# CHIP_tzatziffy_v6.net
KiCad netlist of a schematic drawn in EAGLE
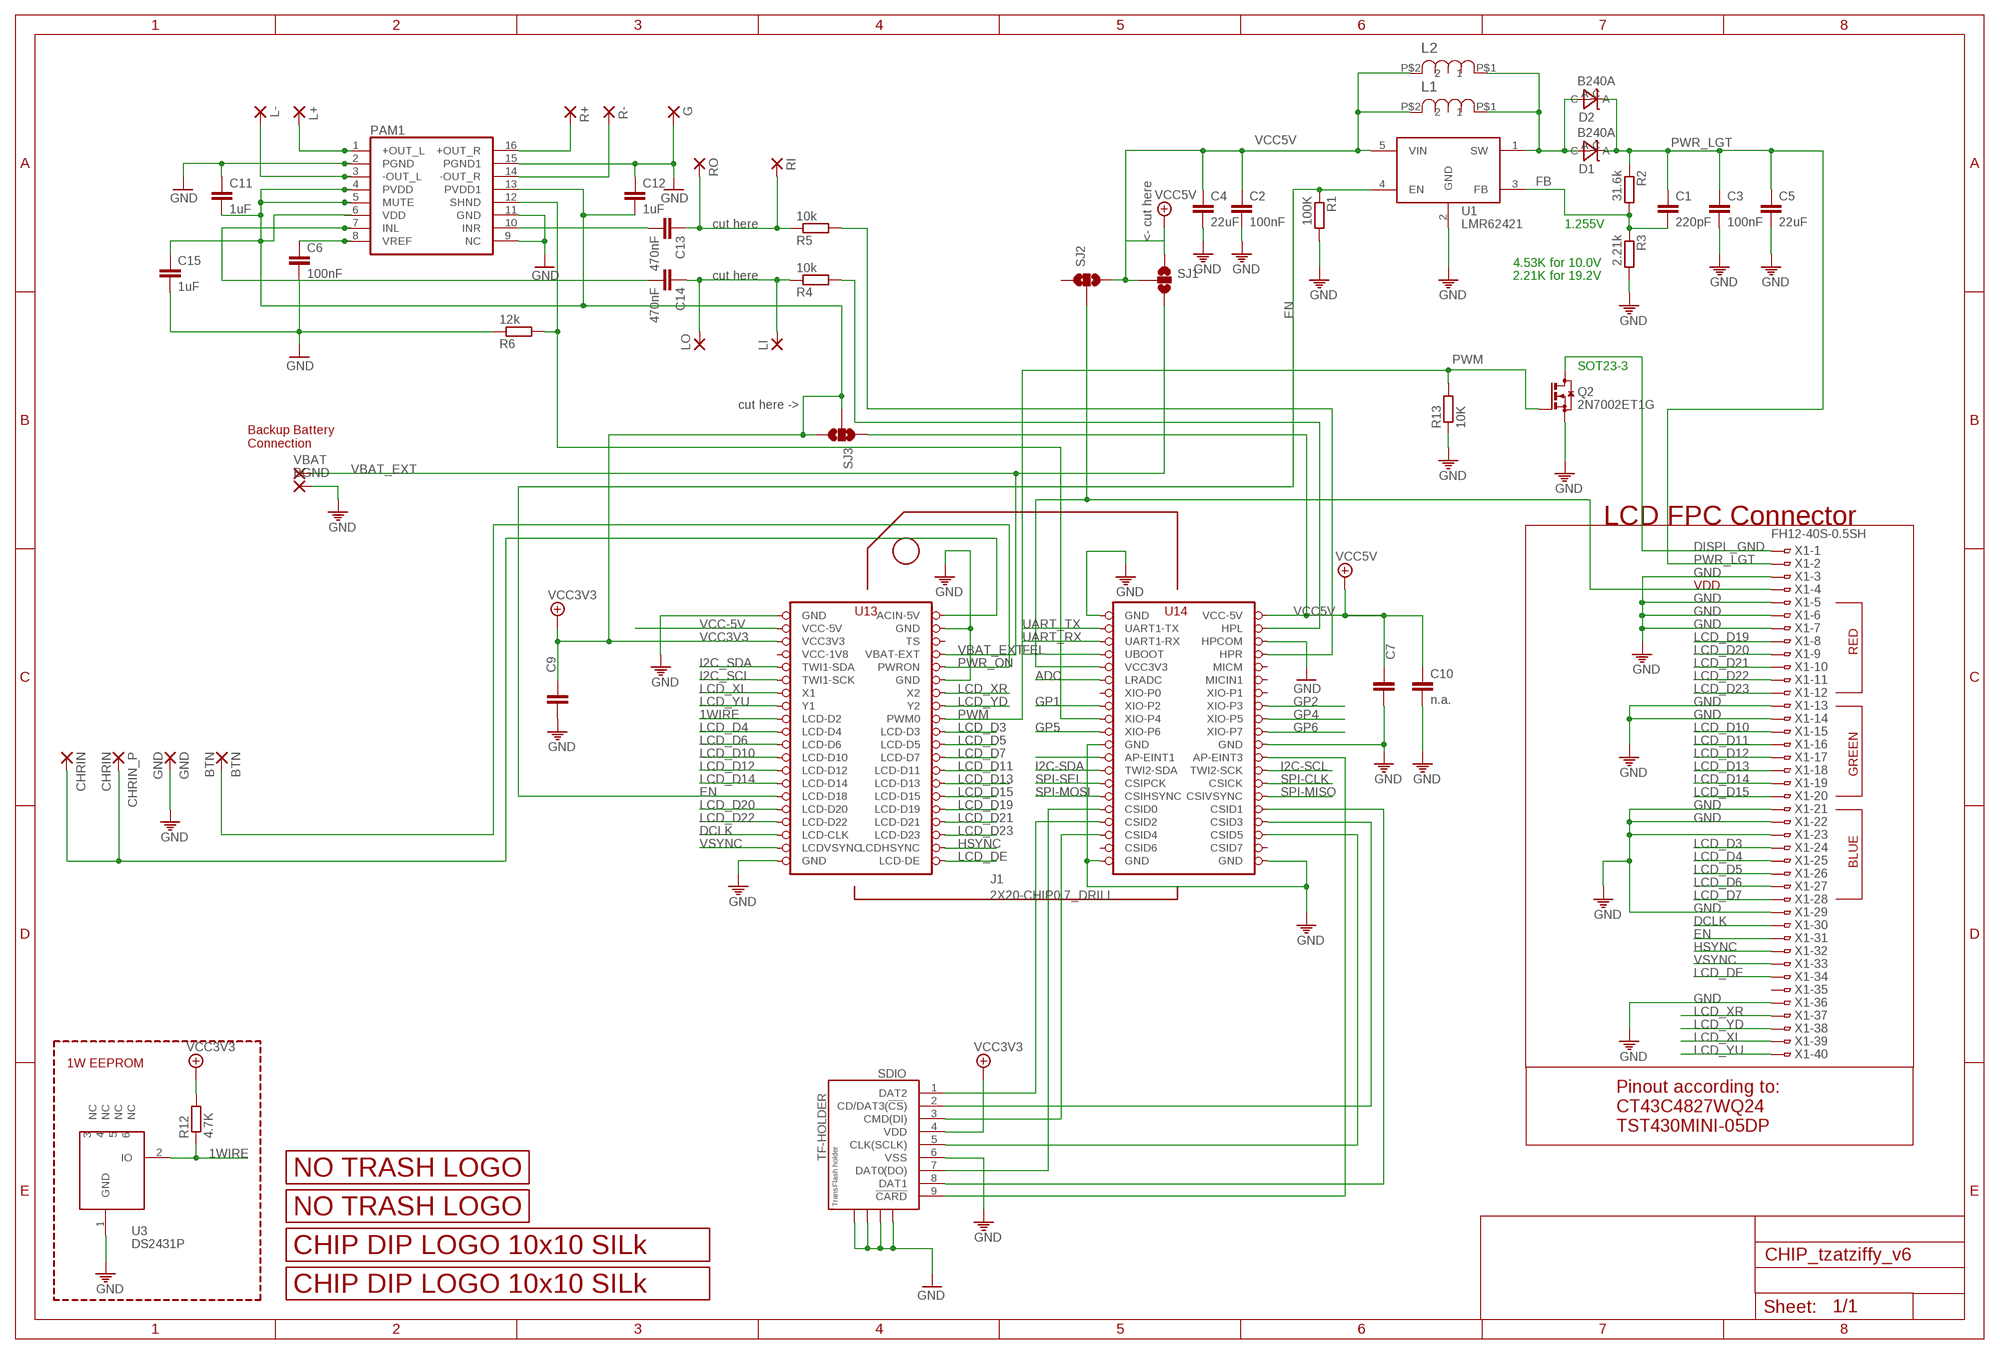
[diagram p0: schematic, sheet 1]

(export (version "E")
  (design (tool "Eeschema 10.0.6"))
  (components
    (comp (ref "BGND")
      (value "1,6/0,8")
      (footprint "eagle-import:1,6_0,8")
      (libsource (lib "eagle-import") (part "1,6/0,8"))
    )
    (comp (ref "BTN")
      (value "BTN")
      (footprint "eagle-import:SMD2,54-5,08")
      (libsource (lib "eagle-import") (part "SMD5"))
    )
    (comp (ref "C1")
      (value "220pF")
      (footprint "eagle-import:C0805")
      (libsource (lib "eagle-import") (part "C-EUC0805"))
    )
    (comp (ref "C2")
      (value "100nF")
      (footprint "eagle-import:C0805")
      (libsource (lib "eagle-import") (part "C-EUC0805"))
    )
    (comp (ref "C3")
      (value "100nF")
      (footprint "eagle-import:C0805")
      (libsource (lib "eagle-import") (part "C-EUC0805"))
    )
    (comp (ref "C4")
      (value "22uF")
      (footprint "eagle-import:C1206")
      (libsource (lib "eagle-import") (part "C-EUC1206"))
    )
    (comp (ref "C5")
      (value "22uF")
      (footprint "eagle-import:C1206")
      (libsource (lib "eagle-import") (part "C-EUC1206"))
    )
    (comp (ref "C6")
      (value "100nF")
      (footprint "eagle-import:C0805")
      (libsource (lib "eagle-import") (part "C-EUC0805"))
    )
    (comp (ref "C7")
      (value "n.a.")
      (footprint "eagle-import:C0805")
      (libsource (lib "eagle-import") (part "C-EUC0805"))
    )
    (comp (ref "C9")
      (value "n.a.")
      (footprint "eagle-import:C0805")
      (libsource (lib "eagle-import") (part "C-EUC0805"))
    )
    (comp (ref "C10")
      (value "n.a.")
      (footprint "eagle-import:C0805")
      (libsource (lib "eagle-import") (part "C-EUC0805"))
    )
    (comp (ref "C11")
      (value "1uF")
      (footprint "eagle-import:C0805")
      (libsource (lib "eagle-import") (part "C-EUC0805"))
    )
    (comp (ref "C12")
      (value "1uF")
      (footprint "eagle-import:C0805")
      (libsource (lib "eagle-import") (part "C-EUC0805"))
    )
    (comp (ref "C13")
      (value "470nF")
      (footprint "eagle-import:C0805")
      (libsource (lib "eagle-import") (part "C-EUC0805"))
    )
    (comp (ref "C14")
      (value "470nF")
      (footprint "eagle-import:C0805")
      (libsource (lib "eagle-import") (part "C-EUC0805"))
    )
    (comp (ref "C15")
      (value "1uF")
      (footprint "eagle-import:C0805")
      (libsource (lib "eagle-import") (part "C-EUC0805"))
    )
    (comp (ref "CHRIN")
      (value "1,6/0,8")
      (footprint "eagle-import:1,6_0,8")
      (libsource (lib "eagle-import") (part "1,6/0,8"))
    )
    (comp (ref "CHRIN_P")
      (value "CHRIN")
      (footprint "eagle-import:SMD2,54-5,08")
      (libsource (lib "eagle-import") (part "SMD5"))
    )
    (comp (ref "D1")
      (value "B240A")
      (footprint "eagle-import:DO-214AC")
      (fields (field (name "MFG") "DIGIKEY") (field (name "VENDOR_PART_NUMBER") "B240A-13-F"))
      (libsource (lib "eagle-import") (part "DIODE_SCHTKY_B240"))
    )
    (comp (ref "D2")
      (value "B240A")
      (footprint "eagle-import:DO-214AC")
      (fields (field (name "MFG") "DIGIKEY") (field (name "VENDOR_PART_NUMBER") "B240A-13-F"))
      (libsource (lib "eagle-import") (part "DIODE_SCHTKY_B240"))
    )
    (comp (ref "G")
      (value "1,6/0,8")
      (footprint "eagle-import:1,6_0,8")
      (libsource (lib "eagle-import") (part "1,6/0,8"))
    )
    (comp (ref "GND")
      (value "GND")
      (footprint "eagle-import:SMD2,54-5,08")
      (libsource (lib "eagle-import") (part "SMD5"))
    )
    (comp (ref "J1")
      (value "2X20-CHIP0.7_DRILL")
      (footprint "eagle-import:2X20CHIP_NOOFFSET-TH_0.7")
      (libsource (lib "eagle-import") (part "2X20-CHIP0.7_DRILL"))
    )
    (comp (ref "L+")
      (value "1,6/0,8")
      (footprint "eagle-import:1,6_0,8")
      (libsource (lib "eagle-import") (part "1,6/0,8"))
    )
    (comp (ref "L-")
      (value "1,6/0,8")
      (footprint "eagle-import:1,6_0,8")
      (libsource (lib "eagle-import") (part "1,6/0,8"))
    )
    (comp (ref "L1")
      (value "SRN6045-100M")
      (footprint "eagle-import:SRN6045")
      (fields (field (name "MFG") "DIGIKEY"))
      (libsource (lib "eagle-import") (part "SRN6045-100M"))
    )
    (comp (ref "L2")
      (value "SRN6045-100M")
      (footprint "eagle-import:SRN6045")
      (fields (field (name "MFG") "DIGIKEY"))
      (libsource (lib "eagle-import") (part "SRN6045-100M"))
    )
    (comp (ref "LI")
      (value "1,6/0,8")
      (footprint "eagle-import:1,6_0,8")
      (libsource (lib "eagle-import") (part "1,6/0,8"))
    )
    (comp (ref "LO")
      (value "1,6/0,8")
      (footprint "eagle-import:1,6_0,8")
      (libsource (lib "eagle-import") (part "1,6/0,8"))
    )
    (comp (ref "PAM1")
      (value "PAM8403")
      (footprint "eagle-import:SOP-16")
      (libsource (lib "eagle-import") (part "PAM8403"))
    )
    (comp (ref "Q2")
      (value "2N7002ET1G")
      (footprint "eagle-import:SOT23")
      (libsource (lib "eagle-import") (part "BSS123"))
    )
    (comp (ref "R+")
      (value "1,6/0,8")
      (footprint "eagle-import:1,6_0,8")
      (libsource (lib "eagle-import") (part "1,6/0,8"))
    )
    (comp (ref "R-")
      (value "1,6/0,8")
      (footprint "eagle-import:1,6_0,8")
      (libsource (lib "eagle-import") (part "1,6/0,8"))
    )
    (comp (ref "R1")
      (value "100K")
      (footprint "eagle-import:M0805")
      (libsource (lib "eagle-import") (part "R-EU_M0805"))
    )
    (comp (ref "R2")
      (value "31.6k")
      (footprint "eagle-import:M0805")
      (libsource (lib "eagle-import") (part "R-EU_M0805"))
    )
    (comp (ref "R3")
      (value "2.21k")
      (footprint "eagle-import:M0805")
      (libsource (lib "eagle-import") (part "R-EU_M0805"))
    )
    (comp (ref "R4")
      (value "10k")
      (footprint "eagle-import:R0805")
      (libsource (lib "eagle-import") (part "R-EU_R0805"))
    )
    (comp (ref "R5")
      (value "10k")
      (footprint "eagle-import:R0805")
      (libsource (lib "eagle-import") (part "R-EU_R0805"))
    )
    (comp (ref "R6")
      (value "12k")
      (footprint "eagle-import:R0805")
      (libsource (lib "eagle-import") (part "R-EU_R0805"))
    )
    (comp (ref "R12")
      (value "4.7K")
      (footprint "eagle-import:M0805")
      (libsource (lib "eagle-import") (part "R-EU_M0805"))
    )
    (comp (ref "R13")
      (value "10K")
      (footprint "eagle-import:M0805")
      (libsource (lib "eagle-import") (part "R-EU_M0805"))
    )
    (comp (ref "RI")
      (value "1,6/0,8")
      (footprint "eagle-import:1,6_0,8")
      (libsource (lib "eagle-import") (part "1,6/0,8"))
    )
    (comp (ref "RO")
      (value "1,6/0,8")
      (footprint "eagle-import:1,6_0,8")
      (libsource (lib "eagle-import") (part "1,6/0,8"))
    )
    (comp (ref "SDIO")
      (value "TF-HOLDER")
      (footprint "eagle-import:TF-PULL")
      (libsource (lib "eagle-import") (part "TF-HOLDER"))
    )
    (comp (ref "SJ1")
      (value "SOLDERJUMPER_2WAYT")
      (footprint "eagle-import:SJ_2")
      (libsource (lib "eagle-import") (part "SOLDERJUMPER_2WAYT"))
    )
    (comp (ref "SJ2")
      (value "SOLDERJUMPER_2WAYT")
      (footprint "eagle-import:SJ_2")
      (libsource (lib "eagle-import") (part "SOLDERJUMPER_2WAYT"))
    )
    (comp (ref "SJ3")
      (value "SOLDERJUMPER_2WAYT")
      (footprint "eagle-import:SJ_2")
      (libsource (lib "eagle-import") (part "SOLDERJUMPER_2WAYT"))
    )
    (comp (ref "U$2")
      (value "LOGO_10X10_SILK")
      (footprint "eagle-import:LOGO2_10X10_SILK")
      (libsource (lib "eagle-import") (part "LOGO_10X10_SILK"))
    )
    (comp (ref "U$3")
      (value "LOGO_NO_TRASHROHS")
      (footprint "eagle-import:LOGO_ROHS_SYM")
      (libsource (lib "eagle-import") (part "LOGO_NO_TRASHROHS"))
    )
    (comp (ref "U$4")
      (value "LOGO_NO_TRASHNO_TRASH")
      (footprint "eagle-import:LOGO_ROHS_NO_TRASH")
      (libsource (lib "eagle-import") (part "LOGO_NO_TRASHNO_TRASH"))
    )
    (comp (ref "U$5")
      (value "LOGO_10X10_SILK")
      (footprint "eagle-import:LOGO2_10X10_SILK")
      (libsource (lib "eagle-import") (part "LOGO_10X10_SILK"))
    )
    (comp (ref "U1")
      (value "LMR62421")
      (footprint "eagle-import:SOT23-5")
      (fields (field (name "MFG") "DIGIKEY") (field (name "VENDOR_PART_NUMBER") "LMR62421XMFE/NOPB"))
      (libsource (lib "eagle-import") (part "LMR62421"))
    )
    (comp (ref "U3")
      (value "DS2431P")
      (footprint "eagle-import:TSOC6")
      (fields (field (name "MFG") "DIGIKEY") (field (name "VENDOR_PART_NUMBER") "DS2431P+T&R"))
      (libsource (lib "eagle-import") (part "DS2431P"))
    )
    (comp (ref "VBAT")
      (value "1,6/0,8")
      (footprint "eagle-import:1,6_0,8")
      (libsource (lib "eagle-import") (part "1,6/0,8"))
    )
    (comp (ref "X1")
      (value "FH12-40S-0.5SH")
      (footprint "eagle-import:FH12-40S-0.5SH")
      (fields (field (name "MFG") "DIGIKEY") (field (name "VENDOR_PART_NUMBER") "FH12-40S-0.5SH(55)"))
      (libsource (lib "eagle-import") (part "FH12-40S-0.5SH"))
    )
  )
  (nets
    (net (code "1") (name "/1WIRE") (class "Default")
      (node (ref "J1") (pin "LCD-D2") (pinfunction "LCD-D2_LCD-D2") (pintype "passive"))
      (node (ref "R12") (pin "1") (pinfunction "1_1") (pintype "passive"))
      (node (ref "U3") (pin "2") (pinfunction "IO_2") (pintype "bidirectional"))
    )
    (net (code "2") (name "/ADC") (class "Default")
      (node (ref "J1") (pin "LRADC") (pinfunction "LRADC_LRADC") (pintype "passive"))
    )
    (net (code "3") (name "/DCLK") (class "Default")
      (node (ref "J1") (pin "LCD-CLK") (pinfunction "LCD-CLK_LCD-CLK") (pintype "passive"))
      (node (ref "X1") (pin "30") (pinfunction "1_30") (pintype "passive"))
    )
    (net (code "4") (name "/DISPL_GND") (class "Default")
      (node (ref "Q2") (pin "3") (pinfunction "D_3") (pintype "passive"))
      (node (ref "X1") (pin "1") (pinfunction "1_1") (pintype "passive"))
    )
    (net (code "5") (name "/EN") (class "Default")
      (node (ref "J1") (pin "LCD-D18") (pinfunction "LCD-D18_LCD-D18") (pintype "passive"))
      (node (ref "R1") (pin "1") (pinfunction "1_1") (pintype "passive"))
      (node (ref "U1") (pin "4") (pinfunction "EN_4") (pintype "bidirectional"))
      (node (ref "X1") (pin "31") (pinfunction "1_31") (pintype "passive"))
    )
    (net (code "6") (name "/FB") (class "Default")
      (node (ref "C1") (pin "2") (pinfunction "2_2") (pintype "passive"))
      (node (ref "R2") (pin "2") (pinfunction "2_2") (pintype "passive"))
      (node (ref "R3") (pin "1") (pinfunction "1_1") (pintype "passive"))
      (node (ref "U1") (pin "3") (pinfunction "FB_3") (pintype "bidirectional"))
    )
    (net (code "7") (name "/FEL") (class "Default")
      (node (ref "J1") (pin "FEL") (pinfunction "UBOOT_FEL") (pintype "passive"))
    )
    (net (code "8") (name "/GP1") (class "Default")
      (node (ref "J1") (pin "XIO-P2") (pinfunction "XIO-P2_XIO-P2") (pintype "passive"))
    )
    (net (code "9") (name "/GP2") (class "Default")
      (node (ref "J1") (pin "XIO-P3") (pinfunction "XIO-P3_XIO-P3") (pintype "passive"))
    )
    (net (code "10") (name "/GP4") (class "Default")
      (node (ref "J1") (pin "XIO-P5") (pinfunction "XIO-P5_XIO-P5") (pintype "passive"))
    )
    (net (code "11") (name "/GP5") (class "Default")
      (node (ref "J1") (pin "XIO-P6") (pinfunction "XIO-P6_XIO-P6") (pintype "passive"))
    )
    (net (code "12") (name "/GP6") (class "Default")
      (node (ref "J1") (pin "XIO-P7") (pinfunction "XIO-P7_XIO-P7") (pintype "passive"))
    )
    (net (code "13") (name "/HSYNC") (class "Default")
      (node (ref "J1") (pin "LCD-HSYNC") (pinfunction "LCDHSYNC_LCD-HSYNC") (pintype "passive"))
      (node (ref "X1") (pin "32") (pinfunction "1_32") (pintype "passive"))
    )
    (net (code "14") (name "/I2C-SCL") (class "Default")
      (node (ref "J1") (pin "TWI2-SCK") (pinfunction "TWI2-SCK_TWI2-SCK") (pintype "passive"))
    )
    (net (code "15") (name "/I2C-SDA") (class "Default")
      (node (ref "J1") (pin "TWI2-SDA") (pinfunction "TWI2-SDA_TWI2-SDA") (pintype "passive"))
    )
    (net (code "16") (name "/I2C_SCL") (class "Default")
      (node (ref "J1") (pin "TWI1-SCK") (pinfunction "TWI1-SCK_TWI1-SCK") (pintype "passive"))
    )
    (net (code "17") (name "/I2C_SDA") (class "Default")
      (node (ref "J1") (pin "TWI1-SDA") (pinfunction "TWI1-SDA_TWI1-SDA") (pintype "passive"))
    )
    (net (code "18") (name "/LCD_D3") (class "Default")
      (node (ref "J1") (pin "LCD-D3") (pinfunction "LCD-D3_LCD-D3") (pintype "passive"))
      (node (ref "X1") (pin "24") (pinfunction "1_24") (pintype "passive"))
    )
    (net (code "19") (name "/LCD_D4") (class "Default")
      (node (ref "J1") (pin "LCD-D4") (pinfunction "LCD-D4_LCD-D4") (pintype "passive"))
      (node (ref "X1") (pin "25") (pinfunction "1_25") (pintype "passive"))
    )
    (net (code "20") (name "/LCD_D5") (class "Default")
      (node (ref "J1") (pin "LCD-D5") (pinfunction "LCD-D5_LCD-D5") (pintype "passive"))
      (node (ref "X1") (pin "26") (pinfunction "1_26") (pintype "passive"))
    )
    (net (code "21") (name "/LCD_D6") (class "Default")
      (node (ref "J1") (pin "LCD-D6") (pinfunction "LCD-D6_LCD-D6") (pintype "passive"))
      (node (ref "X1") (pin "27") (pinfunction "1_27") (pintype "passive"))
    )
    (net (code "22") (name "/LCD_D7") (class "Default")
      (node (ref "J1") (pin "LCD-D7") (pinfunction "LCD-D7_LCD-D7") (pintype "passive"))
      (node (ref "X1") (pin "28") (pinfunction "1_28") (pintype "passive"))
    )
    (net (code "23") (name "/LCD_D10") (class "Default")
      (node (ref "J1") (pin "LCD-D10") (pinfunction "LCD-D10_LCD-D10") (pintype "passive"))
      (node (ref "X1") (pin "15") (pinfunction "1_15") (pintype "passive"))
    )
    (net (code "24") (name "/LCD_D11") (class "Default")
      (node (ref "J1") (pin "LCD-D11") (pinfunction "LCD-D11_LCD-D11") (pintype "passive"))
      (node (ref "X1") (pin "16") (pinfunction "1_16") (pintype "passive"))
    )
    (net (code "25") (name "/LCD_D12") (class "Default")
      (node (ref "J1") (pin "LCD-D12") (pinfunction "LCD-D12_LCD-D12") (pintype "passive"))
      (node (ref "X1") (pin "17") (pinfunction "1_17") (pintype "passive"))
    )
    (net (code "26") (name "/LCD_D13") (class "Default")
      (node (ref "J1") (pin "LCD-D13") (pinfunction "LCD-D13_LCD-D13") (pintype "passive"))
      (node (ref "X1") (pin "18") (pinfunction "1_18") (pintype "passive"))
    )
    (net (code "27") (name "/LCD_D14") (class "Default")
      (node (ref "J1") (pin "LCD-D14") (pinfunction "LCD-D14_LCD-D14") (pintype "passive"))
      (node (ref "X1") (pin "19") (pinfunction "1_19") (pintype "passive"))
    )
    (net (code "28") (name "/LCD_D15") (class "Default")
      (node (ref "J1") (pin "LCD-D15") (pinfunction "LCD-D15_LCD-D15") (pintype "passive"))
      (node (ref "X1") (pin "20") (pinfunction "1_20") (pintype "passive"))
    )
    (net (code "29") (name "/LCD_D19") (class "Default")
      (node (ref "J1") (pin "LCD-D19") (pinfunction "LCD-D19_LCD-D19") (pintype "passive"))
      (node (ref "X1") (pin "8") (pinfunction "1_8") (pintype "passive"))
    )
    (net (code "30") (name "/LCD_D20") (class "Default")
      (node (ref "J1") (pin "LCD-D20") (pinfunction "LCD-D20_LCD-D20") (pintype "passive"))
      (node (ref "X1") (pin "9") (pinfunction "1_9") (pintype "passive"))
    )
    (net (code "31") (name "/LCD_D21") (class "Default")
      (node (ref "J1") (pin "LCD-D21") (pinfunction "LCD-D21_LCD-D21") (pintype "passive"))
      (node (ref "X1") (pin "10") (pinfunction "1_10") (pintype "passive"))
    )
    (net (code "32") (name "/LCD_D22") (class "Default")
      (node (ref "J1") (pin "LCD-D22") (pinfunction "LCD-D22_LCD-D22") (pintype "passive"))
      (node (ref "X1") (pin "11") (pinfunction "1_11") (pintype "passive"))
    )
    (net (code "33") (name "/LCD_D23") (class "Default")
      (node (ref "J1") (pin "LCD-D23") (pinfunction "LCD-D23_LCD-D23") (pintype "passive"))
      (node (ref "X1") (pin "12") (pinfunction "1_12") (pintype "passive"))
    )
    (net (code "34") (name "/LCD_DE") (class "Default")
      (node (ref "J1") (pin "LCD-DE") (pinfunction "LCD-DE_LCD-DE") (pintype "passive"))
      (node (ref "X1") (pin "34") (pinfunction "1_34") (pintype "passive"))
    )
    (net (code "35") (name "/LCD_XL") (class "Default")
      (node (ref "J1") (pin "X1") (pinfunction "X1_X1") (pintype "passive"))
      (node (ref "X1") (pin "39") (pinfunction "1_39") (pintype "passive"))
    )
    (net (code "36") (name "/LCD_XR") (class "Default")
      (node (ref "J1") (pin "X2") (pinfunction "X2_X2") (pintype "passive"))
      (node (ref "X1") (pin "37") (pinfunction "1_37") (pintype "passive"))
    )
    (net (code "37") (name "/LCD_YD") (class "Default")
      (node (ref "J1") (pin "Y2") (pinfunction "Y2_Y2") (pintype "passive"))
      (node (ref "X1") (pin "38") (pinfunction "1_38") (pintype "passive"))
    )
    (net (code "38") (name "/LCD_YU") (class "Default")
      (node (ref "J1") (pin "Y1") (pinfunction "Y1_Y1") (pintype "passive"))
      (node (ref "X1") (pin "40") (pinfunction "1_40") (pintype "passive"))
    )
    (net (code "39") (name "/PWM") (class "Default")
      (node (ref "J1") (pin "PWM0") (pinfunction "PWM0_PWM0") (pintype "passive"))
      (node (ref "Q2") (pin "1") (pinfunction "G_1") (pintype "passive"))
      (node (ref "R13") (pin "2") (pinfunction "2_2") (pintype "passive"))
    )
    (net (code "40") (name "/PWR_LGT") (class "Default")
      (node (ref "C1") (pin "1") (pinfunction "1_1") (pintype "passive"))
      (node (ref "C3") (pin "1") (pinfunction "1_1") (pintype "passive"))
      (node (ref "C5") (pin "1") (pinfunction "1_1") (pintype "passive"))
      (node (ref "D1") (pin "C") (pinfunction "C_C") (pintype "bidirectional"))
      (node (ref "D2") (pin "C") (pinfunction "C_C") (pintype "bidirectional"))
      (node (ref "R2") (pin "1") (pinfunction "1_1") (pintype "passive"))
      (node (ref "X1") (pin "2") (pinfunction "1_2") (pintype "passive"))
    )
    (net (code "41") (name "/PWR_ON") (class "Default")
      (node (ref "BTN") (pin "1") (pinfunction "P_1") (pintype "passive"))
      (node (ref "J1") (pin "PWRON") (pinfunction "PWRON_PWRON") (pintype "passive"))
    )
    (net (code "42") (name "/SPI-CLK") (class "Default")
      (node (ref "J1") (pin "CSICK") (pinfunction "CSICK_CSICK") (pintype "passive"))
    )
    (net (code "43") (name "/SPI-MISO") (class "Default")
      (node (ref "J1") (pin "CSIVSYNC") (pinfunction "CSIVSYNC_CSIVSYNC") (pintype "passive"))
    )
    (net (code "44") (name "/SPI-MOSI") (class "Default")
      (node (ref "J1") (pin "CSIHSYNC") (pinfunction "CSIHSYNC_CSIHSYNC") (pintype "passive"))
    )
    (net (code "45") (name "/SPI-SEL") (class "Default")
      (node (ref "J1") (pin "CSIPCK") (pinfunction "CSIPCK_CSIPCK") (pintype "passive"))
    )
    (net (code "46") (name "/UART_RX") (class "Default")
      (node (ref "J1") (pin "UART1-RX") (pinfunction "UART1-RX_UART1-RX") (pintype "passive"))
    )
    (net (code "47") (name "/UART_TX") (class "Default")
      (node (ref "J1") (pin "UART1-TX") (pinfunction "UART1-TX_UART1-TX") (pintype "passive"))
    )
    (net (code "48") (name "/VBAT_EXT") (class "Default")
      (node (ref "J1") (pin "BAT") (pinfunction "VBAT-EXT_BAT") (pintype "passive"))
      (node (ref "SJ1") (pin "3") (pinfunction "3_3") (pintype "passive"))
      (node (ref "VBAT") (pin "1") (pinfunction "P_1") (pintype "passive"))
    )
    (net (code "49") (name "/VCC-1V8") (class "Default")
      (node (ref "J1") (pin "VCC1V8") (pinfunction "VCC-1V8_VCC1V8") (pintype "power_in"))
    )
    (net (code "50") (name "/VCC-5V") (class "Default")
      (node (ref "J1") (pin "VCC5V@0") (pinfunction "VCC-5V_VCC5V@0") (pintype "power_in"))
    )
    (net (code "51") (name "/VSYNC") (class "Default")
      (node (ref "J1") (pin "LCD-VSYNC") (pinfunction "LCDVSYNC_LCD-VSYNC") (pintype "passive"))
      (node (ref "X1") (pin "33") (pinfunction "1_33") (pintype "passive"))
    )
    (net (code "52") (name "GND") (class "Default")
      (node (ref "BGND") (pin "1") (pinfunction "P_1") (pintype "passive"))
      (node (ref "C10") (pin "2") (pinfunction "2_2") (pintype "passive"))
      (node (ref "C11") (pin "1") (pinfunction "1_1") (pintype "passive"))
      (node (ref "C12") (pin "1") (pinfunction "1_1") (pintype "passive"))
      (node (ref "C15") (pin "2") (pinfunction "2_2") (pintype "passive"))
      (node (ref "C2") (pin "2") (pinfunction "2_2") (pintype "passive"))
      (node (ref "C3") (pin "2") (pinfunction "2_2") (pintype "passive"))
      (node (ref "C4") (pin "2") (pinfunction "2_2") (pintype "passive"))
      (node (ref "C5") (pin "2") (pinfunction "2_2") (pintype "passive"))
      (node (ref "C6") (pin "2") (pinfunction "2_2") (pintype "passive"))
      (node (ref "C7") (pin "2") (pinfunction "2_2") (pintype "passive"))
      (node (ref "C9") (pin "2") (pinfunction "2_2") (pintype "passive"))
      (node (ref "G") (pin "1") (pinfunction "P_1") (pintype "passive"))
      (node (ref "GND") (pin "1") (pinfunction "P_1") (pintype "passive"))
      (node (ref "J1") (pin "GND@1") (pinfunction "GND_GND@1") (pintype "power_in"))
      (node (ref "J1") (pin "GND@10") (pinfunction "GND_GND@10") (pintype "power_in"))
      (node (ref "J1") (pin "GND@2") (pinfunction "GND_GND@2") (pintype "power_in"))
      (node (ref "J1") (pin "GND@3") (pinfunction "GND_GND@3") (pintype "power_in"))
      (node (ref "J1") (pin "GND@4") (pinfunction "GND_GND@4") (pintype "power_in"))
      (node (ref "J1") (pin "GND@5") (pinfunction "GND_GND@5") (pintype "power_in"))
      (node (ref "J1") (pin "GND@6") (pinfunction "GND_GND@6") (pintype "power_in"))
      (node (ref "J1") (pin "GND@7") (pinfunction "GND_GND@7") (pintype "power_in"))
      (node (ref "J1") (pin "GND@8") (pinfunction "GND_GND@8") (pintype "power_in"))
      (node (ref "J1") (pin "HPCOM") (pinfunction "HPCOM_HPCOM") (pintype "passive"))
      (node (ref "PAM1") (pin "11") (pinfunction "GND_11") (pintype "output"))
      (node (ref "PAM1") (pin "15") (pinfunction "PGND1_15") (pintype "output"))
      (node (ref "PAM1") (pin "2") (pinfunction "PGND_2") (pintype "input"))
      (node (ref "PAM1") (pin "9") (pinfunction "NC_9") (pintype "output"))
      (node (ref "Q2") (pin "2") (pinfunction "S_2") (pintype "passive"))
      (node (ref "R1") (pin "2") (pinfunction "2_2") (pintype "passive"))
      (node (ref "R13") (pin "1") (pinfunction "1_1") (pintype "passive"))
      (node (ref "R3") (pin "2") (pinfunction "2_2") (pintype "passive"))
      (node (ref "R6") (pin "1") (pinfunction "1_1") (pintype "passive"))
      (node (ref "SDIO") (pin "6") (pinfunction "VSS_6") (pintype "power_in"))
      (node (ref "SDIO") (pin "S1") (pinfunction "S1_S1") (pintype "passive"))
      (node (ref "SDIO") (pin "S2") (pinfunction "S2_S2") (pintype "passive"))
      (node (ref "SDIO") (pin "S3") (pinfunction "S3_S3") (pintype "passive"))
      (node (ref "SDIO") (pin "S4") (pinfunction "S4_S4") (pintype "passive"))
      (node (ref "U1") (pin "2") (pinfunction "GND_2") (pintype "bidirectional"))
      (node (ref "U3") (pin "1") (pinfunction "GND_1") (pintype "bidirectional"))
      (node (ref "X1") (pin "13") (pinfunction "1_13") (pintype "passive"))
      (node (ref "X1") (pin "14") (pinfunction "1_14") (pintype "passive"))
      (node (ref "X1") (pin "21") (pinfunction "1_21") (pintype "passive"))
      (node (ref "X1") (pin "22") (pinfunction "1_22") (pintype "passive"))
      (node (ref "X1") (pin "23") (pinfunction "1_23") (pintype "passive"))
      (node (ref "X1") (pin "29") (pinfunction "1_29") (pintype "passive"))
      (node (ref "X1") (pin "3") (pinfunction "1_3") (pintype "passive"))
      (node (ref "X1") (pin "36") (pinfunction "1_36") (pintype "passive"))
      (node (ref "X1") (pin "5") (pinfunction "1_5") (pintype "passive"))
      (node (ref "X1") (pin "6") (pinfunction "1_6") (pintype "passive"))
      (node (ref "X1") (pin "7") (pinfunction "1_7") (pintype "passive"))
    )
    (net (code "53") (name "Net-(CHRIN-P)") (class "Default")
      (node (ref "CHRIN") (pin "1") (pinfunction "P_1") (pintype "passive"))
      (node (ref "CHRIN_P") (pin "1") (pinfunction "P_1") (pintype "passive"))
      (node (ref "J1") (pin "CHG-IN") (pinfunction "ACIN-5V_CHG-IN") (pintype "passive"))
    )
    (net (code "54") (name "Net-(J1-PadHPL)") (class "Default")
      (node (ref "J1") (pin "HPL") (pinfunction "HPL_HPL") (pintype "passive"))
      (node (ref "R4") (pin "2") (pinfunction "2_2") (pintype "passive"))
    )
    (net (code "55") (name "Net-(J1-PadHPR)") (class "Default")
      (node (ref "J1") (pin "HPR") (pinfunction "HPR_HPR") (pintype "passive"))
      (node (ref "R5") (pin "2") (pinfunction "2_2") (pintype "passive"))
    )
    (net (code "56") (name "Net-(L+-P)") (class "Default")
      (node (ref "L+") (pin "1") (pinfunction "P_1") (pintype "passive"))
      (node (ref "PAM1") (pin "1") (pinfunction "+OUT_L_1") (pintype "input"))
    )
    (net (code "57") (name "Net-(L--P)") (class "Default")
      (node (ref "L-") (pin "1") (pinfunction "P_1") (pintype "passive"))
      (node (ref "PAM1") (pin "3") (pinfunction "-OUT_L_3") (pintype "input"))
    )
    (net (code "58") (name "Net-(L1-1)") (class "Default")
      (node (ref "D1") (pin "A") (pinfunction "A_A") (pintype "bidirectional"))
      (node (ref "D2") (pin "A") (pinfunction "A_A") (pintype "bidirectional"))
      (node (ref "L1") (pin "P$1") (pinfunction "1_P$1") (pintype "passive"))
      (node (ref "L2") (pin "P$1") (pinfunction "1_P$1") (pintype "passive"))
      (node (ref "U1") (pin "1") (pinfunction "SW_1") (pintype "bidirectional"))
    )
    (net (code "59") (name "Net-(LI-P)") (class "Default")
      (node (ref "C14") (pin "1") (pinfunction "1_1") (pintype "passive"))
      (node (ref "LI") (pin "1") (pinfunction "P_1") (pintype "passive"))
      (node (ref "LO") (pin "1") (pinfunction "P_1") (pintype "passive"))
      (node (ref "R4") (pin "1") (pinfunction "1_1") (pintype "passive"))
    )
    (net (code "60") (name "Net-(PAM1-+OUT_R)") (class "Default")
      (node (ref "PAM1") (pin "16") (pinfunction "+OUT_R_16") (pintype "output"))
      (node (ref "R+") (pin "1") (pinfunction "P_1") (pintype "passive"))
    )
    (net (code "61") (name "Net-(PAM1--OUT_R)") (class "Default")
      (node (ref "PAM1") (pin "14") (pinfunction "-OUT_R_14") (pintype "output"))
      (node (ref "R-") (pin "1") (pinfunction "P_1") (pintype "passive"))
    )
    (net (code "62") (name "Net-(PAM1-INL)") (class "Default")
      (node (ref "C14") (pin "2") (pinfunction "2_2") (pintype "passive"))
      (node (ref "PAM1") (pin "7") (pinfunction "INL_7") (pintype "input"))
    )
    (net (code "63") (name "Net-(PAM1-INR)") (class "Default")
      (node (ref "C13") (pin "2") (pinfunction "2_2") (pintype "passive"))
      (node (ref "PAM1") (pin "10") (pinfunction "INR_10") (pintype "output"))
    )
    (net (code "64") (name "Net-(PAM1-SHND)") (class "Default")
      (node (ref "J1") (pin "XIO-P4") (pinfunction "XIO-P4_XIO-P4") (pintype "passive"))
      (node (ref "PAM1") (pin "12") (pinfunction "SHND_12") (pintype "output"))
      (node (ref "R6") (pin "2") (pinfunction "2_2") (pintype "passive"))
    )
    (net (code "65") (name "Net-(PAM1-VREF)") (class "Default")
      (node (ref "C6") (pin "1") (pinfunction "1_1") (pintype "passive"))
      (node (ref "PAM1") (pin "8") (pinfunction "VREF_8") (pintype "input"))
    )
    (net (code "66") (name "Net-(RI-P)") (class "Default")
      (node (ref "C13") (pin "1") (pinfunction "1_1") (pintype "passive"))
      (node (ref "R5") (pin "1") (pinfunction "1_1") (pintype "passive"))
      (node (ref "RI") (pin "1") (pinfunction "P_1") (pintype "passive"))
      (node (ref "RO") (pin "1") (pinfunction "P_1") (pintype "passive"))
    )
    (net (code "67") (name "Net-(SDIO-CD{slash}DAT3(~{CS}))") (class "Default")
      (node (ref "J1") (pin "CSID3") (pinfunction "CSID3_CSID3") (pintype "passive"))
      (node (ref "SDIO") (pin "2") (pinfunction "CD/DAT3(~{CS})_2") (pintype "bidirectional"))
    )
    (net (code "68") (name "Net-(SDIO-CLK(SCLK))") (class "Default")
      (node (ref "J1") (pin "CSID5") (pinfunction "CSID5_CSID5") (pintype "passive"))
      (node (ref "SDIO") (pin "5") (pinfunction "CLK(SCLK)_5") (pintype "input"))
    )
    (net (code "69") (name "Net-(SDIO-CMD(DI))") (class "Default")
      (node (ref "J1") (pin "CSID4") (pinfunction "CSID4_CSID4") (pintype "passive"))
      (node (ref "SDIO") (pin "3") (pinfunction "CMD(DI)_3") (pintype "bidirectional"))
    )
    (net (code "70") (name "Net-(SDIO-DAT0(DO))") (class "Default")
      (node (ref "J1") (pin "CSID0") (pinfunction "CSID0_CSID0") (pintype "passive"))
      (node (ref "SDIO") (pin "7") (pinfunction "DAT0(DO)_7") (pintype "bidirectional"))
    )
    (net (code "71") (name "Net-(SDIO-DAT1)") (class "Default")
      (node (ref "J1") (pin "CSID1") (pinfunction "CSID1_CSID1") (pintype "passive"))
      (node (ref "SDIO") (pin "8") (pinfunction "DAT1_8") (pintype "bidirectional"))
    )
    (net (code "72") (name "Net-(SDIO-DAT2)") (class "Default")
      (node (ref "J1") (pin "CSID2") (pinfunction "CSID2_CSID2") (pintype "passive"))
      (node (ref "SDIO") (pin "1") (pinfunction "DAT2_1") (pintype "bidirectional"))
    )
    (net (code "73") (name "Net-(SDIO-~{CARD})") (class "Default")
      (node (ref "J1") (pin "AP-EINT3") (pinfunction "AP-EINT3_AP-EINT3") (pintype "passive"))
      (node (ref "SDIO") (pin "9") (pinfunction "~{CARD}_9") (pintype "passive"))
    )
    (net (code "74") (name "Net-(X1AH-1)") (class "Default")
      (node (ref "J1") (pin "VCC3V3@1") (pinfunction "VCC3V3_VCC3V3@1") (pintype "power_in"))
      (node (ref "SJ2") (pin "2") (pinfunction "2_2") (pintype "passive"))
      (node (ref "X1") (pin "4") (pinfunction "1_4") (pintype "passive"))
    )
    (net (code "75") (name "VCC3V3") (class "Default")
      (node (ref "C11") (pin "2") (pinfunction "2_2") (pintype "passive"))
      (node (ref "C12") (pin "2") (pinfunction "2_2") (pintype "passive"))
      (node (ref "C15") (pin "1") (pinfunction "1_1") (pintype "passive"))
      (node (ref "C9") (pin "1") (pinfunction "1_1") (pintype "passive"))
      (node (ref "J1") (pin "VCC3V3") (pinfunction "VCC3V3_VCC3V3") (pintype "power_in"))
      (node (ref "PAM1") (pin "13") (pinfunction "PVDD1_13") (pintype "output"))
      (node (ref "PAM1") (pin "4") (pinfunction "PVDD_4") (pintype "input"))
      (node (ref "PAM1") (pin "5") (pinfunction "MUTE_5") (pintype "input"))
      (node (ref "PAM1") (pin "6") (pinfunction "VDD_6") (pintype "input"))
      (node (ref "R12") (pin "2") (pinfunction "2_2") (pintype "passive"))
      (node (ref "SDIO") (pin "4") (pinfunction "VDD_4") (pintype "power_in"))
      (node (ref "SJ3") (pin "2") (pinfunction "2_2") (pintype "passive"))
      (node (ref "SJ3") (pin "3") (pinfunction "3_3") (pintype "passive"))
    )
    (net (code "76") (name "VCC5V") (class "Default")
      (node (ref "C10") (pin "1") (pinfunction "1_1") (pintype "passive"))
      (node (ref "C2") (pin "1") (pinfunction "1_1") (pintype "passive"))
      (node (ref "C4") (pin "1") (pinfunction "1_1") (pintype "passive"))
      (node (ref "C7") (pin "1") (pinfunction "1_1") (pintype "passive"))
      (node (ref "J1") (pin "VCC5V@1") (pinfunction "VCC-5V_VCC5V@1") (pintype "power_in"))
      (node (ref "L1") (pin "P$2") (pinfunction "2_P$2") (pintype "passive"))
      (node (ref "L2") (pin "P$2") (pinfunction "2_P$2") (pintype "passive"))
      (node (ref "SJ1") (pin "1") (pinfunction "1_1") (pintype "passive"))
      (node (ref "SJ1") (pin "2") (pinfunction "2_2") (pintype "passive"))
      (node (ref "SJ2") (pin "3") (pinfunction "3_3") (pintype "passive"))
      (node (ref "SJ3") (pin "1") (pinfunction "1_1") (pintype "passive"))
      (node (ref "U1") (pin "5") (pinfunction "VIN_5") (pintype "bidirectional"))
    )
    (net (code "77") (name "unconnected-(J1-PadAP-EINT1)") (class "Default")
      (node (ref "J1") (pin "AP-EINT1") (pinfunction "AP-EINT1_AP-EINT1") (pintype "passive"))
    )
    (net (code "78") (name "unconnected-(J1-PadCSID6)") (class "Default")
      (node (ref "J1") (pin "CSID6") (pinfunction "CSID6_CSID6") (pintype "passive"))
    )
    (net (code "79") (name "unconnected-(J1-PadCSID7)") (class "Default")
      (node (ref "J1") (pin "CSID7") (pinfunction "CSID7_CSID7") (pintype "passive"))
    )
    (net (code "80") (name "unconnected-(J1-PadMICIN1)") (class "Default")
      (node (ref "J1") (pin "MICIN1") (pinfunction "MICIN1_MICIN1") (pintype "passive"))
    )
    (net (code "81") (name "unconnected-(J1-PadMICM)") (class "Default")
      (node (ref "J1") (pin "MICM") (pinfunction "MICM_MICM") (pintype "passive"))
    )
    (net (code "82") (name "unconnected-(J1-PadTS)") (class "Default")
      (node (ref "J1") (pin "TS") (pinfunction "TS_TS") (pintype "passive"))
    )
    (net (code "83") (name "unconnected-(J1-PadXIO-P0)") (class "Default")
      (node (ref "J1") (pin "XIO-P0") (pinfunction "XIO-P0_XIO-P0") (pintype "passive"))
    )
    (net (code "84") (name "unconnected-(J1-PadXIO-P1)") (class "Default")
      (node (ref "J1") (pin "XIO-P1") (pinfunction "XIO-P1_XIO-P1") (pintype "passive"))
    )
    (net (code "85") (name "unconnected-(SJ2-Pad1)") (class "Default")
      (node (ref "SJ2") (pin "1") (pinfunction "1_1") (pintype "passive"))
    )
    (net (code "86") (name "unconnected-(U3-NC-Pad3)") (class "Default")
      (node (ref "U3") (pin "3") (pinfunction "NC_3") (pintype "bidirectional"))
    )
    (net (code "87") (name "unconnected-(U3-NC-Pad4)") (class "Default")
      (node (ref "U3") (pin "4") (pinfunction "NC_4") (pintype "bidirectional"))
    )
    (net (code "88") (name "unconnected-(U3-NC-Pad5)") (class "Default")
      (node (ref "U3") (pin "5") (pinfunction "NC_5") (pintype "bidirectional"))
    )
    (net (code "89") (name "unconnected-(U3-NC-Pad6)") (class "Default")
      (node (ref "U3") (pin "6") (pinfunction "NC_6") (pintype "bidirectional"))
    )
    (net (code "90") (name "unconnected-(X1AC-1-Pad35)") (class "Default")
      (node (ref "X1") (pin "35") (pinfunction "1_35") (pintype "passive"))
    )
  )
)
